# ATMEGA8.net
KiCad netlist of a schematic drawn in EAGLE
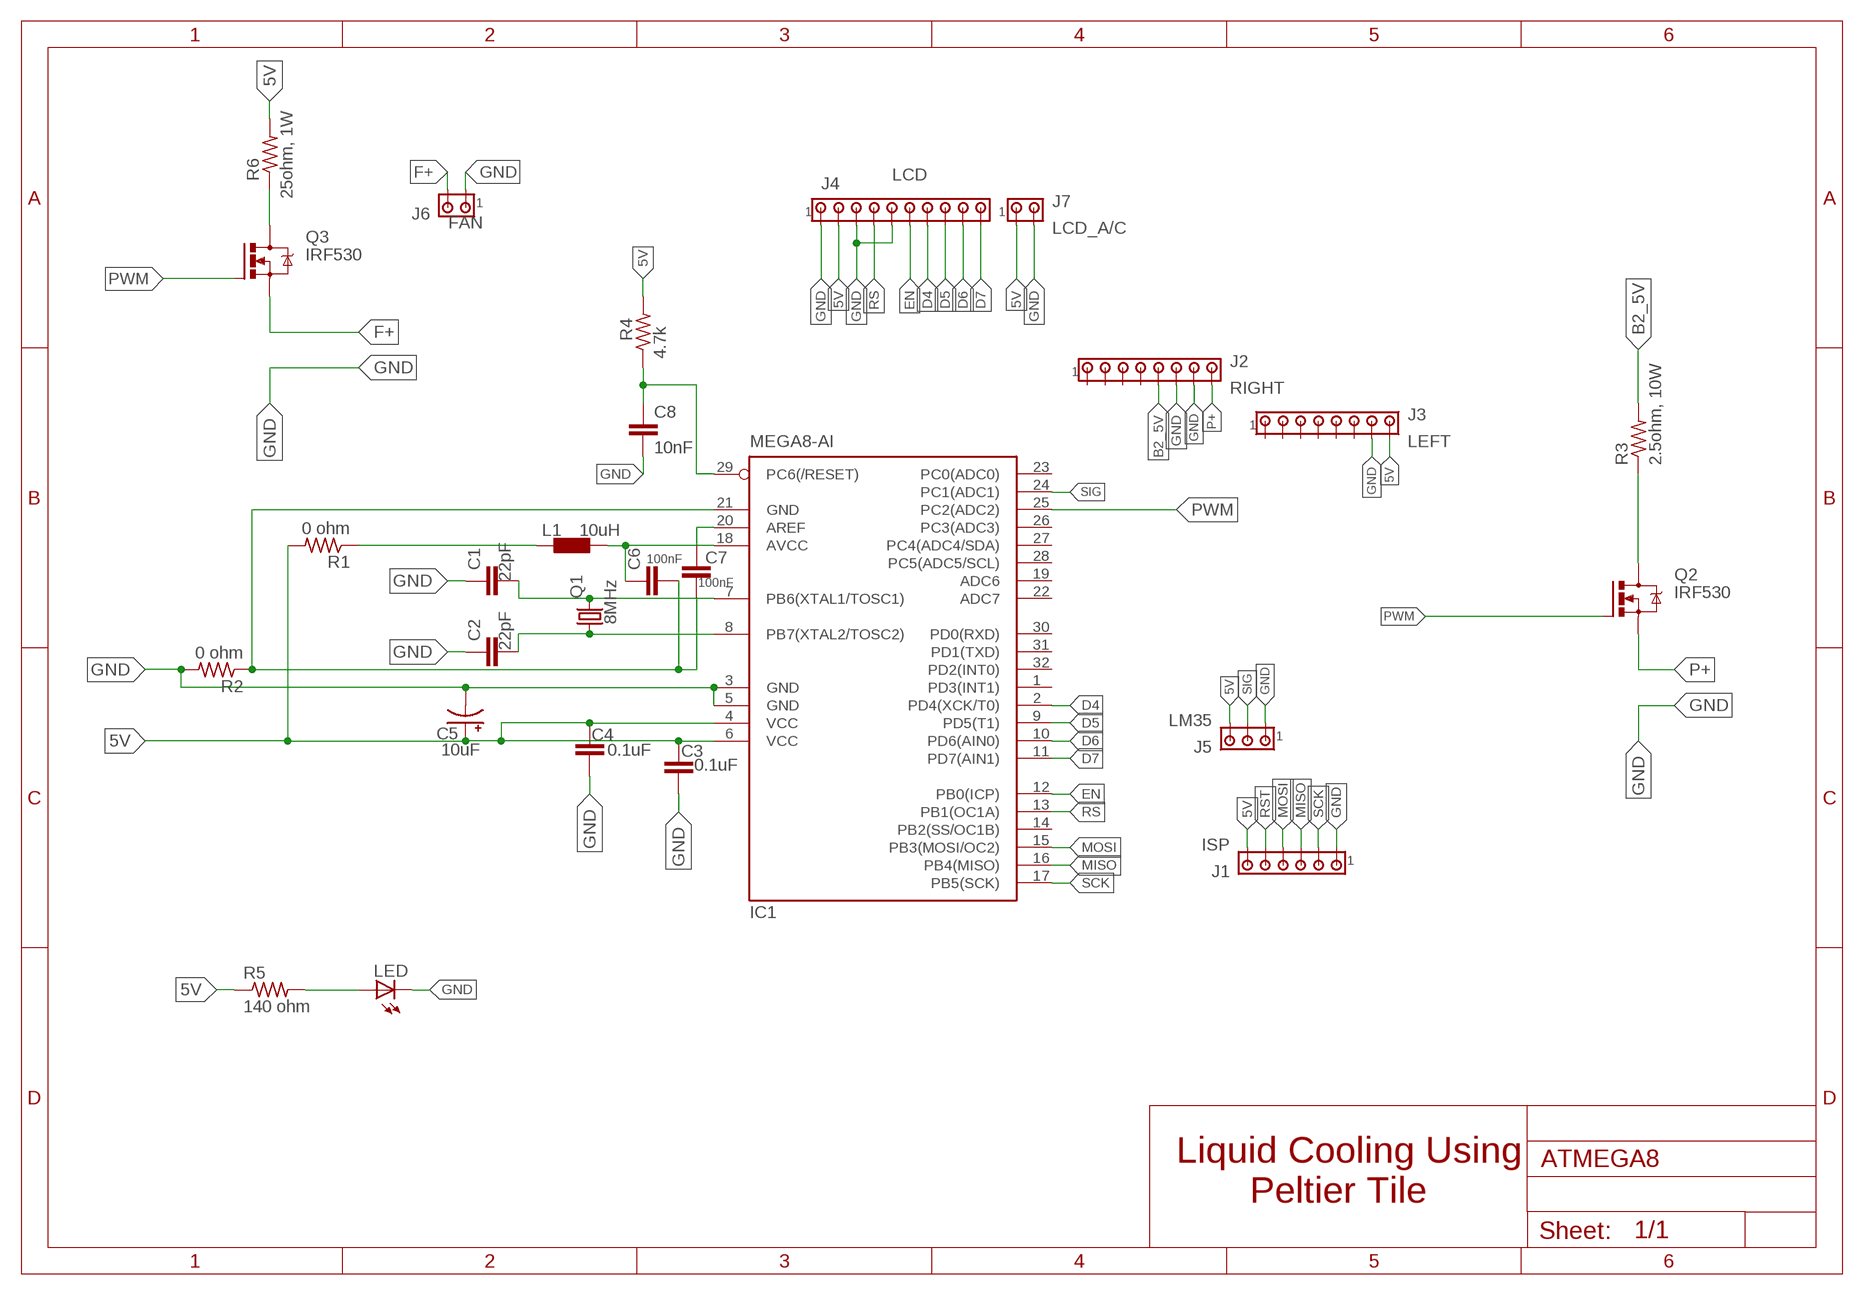
[diagram p0: schematic, sheet 1]

(export (version "E")
  (design (tool "Eeschema 10.0.6"))
  (components
    (comp (ref "C1")
      (value "22pF")
      (footprint "eagle-import:C0805")
      (libsource (lib "eagle-import") (part "C-EUC0805"))
    )
    (comp (ref "C2")
      (value "22pF")
      (footprint "eagle-import:C0805")
      (libsource (lib "eagle-import") (part "C-EUC0805"))
    )
    (comp (ref "C3")
      (value "0.1uF")
      (footprint "eagle-import:C0805")
      (libsource (lib "eagle-import") (part "C-EUC0805"))
    )
    (comp (ref "C4")
      (value "0.1uF")
      (footprint "eagle-import:C0805")
      (libsource (lib "eagle-import") (part "C-EUC0805"))
    )
    (comp (ref "C5")
      (value "10uF")
      (footprint "eagle-import:A_3216-18R")
      (libsource (lib "eagle-import") (part "CPOL-USA/3216-18R"))
    )
    (comp (ref "C6")
      (value "100nF")
      (footprint "eagle-import:C0805")
      (libsource (lib "eagle-import") (part "C-EUC0805"))
    )
    (comp (ref "C7")
      (value "100nF")
      (footprint "eagle-import:C0805")
      (libsource (lib "eagle-import") (part "C-EUC0805"))
    )
    (comp (ref "C8")
      (value "10nF")
      (footprint "eagle-import:C0805")
      (libsource (lib "eagle-import") (part "C-EUC0805"))
    )
    (comp (ref "IC1")
      (value "MEGA8-AI")
      (footprint "eagle-import:TQFP32-08")
      (fields (field (name "MPN") "ATMEGA8-16AU"))
      (libsource (lib "eagle-import") (part "MEGA8-AI"))
    )
    (comp (ref "J1")
      (value "ISP")
      (footprint "eagle-import:10X06MTA")
      (libsource (lib "eagle-import") (part "MTA06-100"))
    )
    (comp (ref "J2")
      (value "RIGHT")
      (footprint "eagle-import:10X08MTA")
      (libsource (lib "eagle-import") (part "MTA08-100"))
    )
    (comp (ref "J3")
      (value "LEFT")
      (footprint "eagle-import:10X08MTA")
      (libsource (lib "eagle-import") (part "MTA08-100"))
    )
    (comp (ref "J4")
      (value "LCD")
      (footprint "eagle-import:10X10MTA")
      (libsource (lib "eagle-import") (part "MTA10-100"))
    )
    (comp (ref "J5")
      (value "LM35")
      (footprint "eagle-import:10X03MTA")
      (libsource (lib "eagle-import") (part "MTA03-100"))
    )
    (comp (ref "J6")
      (value "FAN")
      (footprint "eagle-import:10X02MTA")
      (libsource (lib "eagle-import") (part "MTA02-100"))
    )
    (comp (ref "J7")
      (value "LCD_A/C")
      (footprint "eagle-import:10X02MTA")
      (libsource (lib "eagle-import") (part "MTA02-100"))
    )
    (comp (ref "L1")
      (value "10uH")
      (footprint "eagle-import:0204_7")
      (libsource (lib "eagle-import") (part "L0204/7"))
    )
    (comp (ref "LED")
      (value "RED")
      (footprint "eagle-import:CHIPLED_1206")
      (libsource (lib "eagle-import") (part "LEDCHIPLED_1206"))
    )
    (comp (ref "Q1")
      (value "8MHz")
      (footprint "eagle-import:CSM-7X-DU")
      (libsource (lib "eagle-import") (part "CSM-7X-DU"))
    )
    (comp (ref "Q2")
      (value "IRF530")
      (footprint "eagle-import:TO220BV")
      (libsource (lib "eagle-import") (part "IRF530"))
    )
    (comp (ref "Q3")
      (value "IRF530")
      (footprint "eagle-import:TO220BV")
      (libsource (lib "eagle-import") (part "IRF530"))
    )
    (comp (ref "R1")
      (value "0 ohm")
      (footprint "eagle-import:M0805")
      (libsource (lib "eagle-import") (part "rcl_334_R-US_M0805"))
    )
    (comp (ref "R2")
      (value "0 ohm")
      (footprint "eagle-import:M0805")
      (libsource (lib "eagle-import") (part "rcl_334_R-US_M0805"))
    )
    (comp (ref "R3")
      (value "2.5ohm, 10W")
      (footprint "eagle-import:0207_9")
      (libsource (lib "eagle-import") (part "R-US_0207/9"))
    )
    (comp (ref "R4")
      (value "4.7k")
      (footprint "eagle-import:M0805")
      (libsource (lib "eagle-import") (part "rcl_334_R-US_M0805"))
    )
    (comp (ref "R5")
      (value "140 ohm")
      (footprint "eagle-import:M0805")
      (libsource (lib "eagle-import") (part "rcl_334_R-US_M0805"))
    )
    (comp (ref "R6")
      (value "25ohm, 1W")
      (footprint "eagle-import:0207_10")
      (libsource (lib "eagle-import") (part "R-US_0207/10"))
    )
  )
  (nets
    (net (code "1") (name "5V") (class "Default")
      (node (ref "C3") (pin "1") (pinfunction "1_1") (pintype "passive"))
      (node (ref "C4") (pin "1") (pinfunction "1_1") (pintype "passive"))
      (node (ref "C5") (pin "+") (pinfunction "+_+") (pintype "passive"))
      (node (ref "IC1") (pin "4") (pinfunction "VCC_4") (pintype "power_in"))
      (node (ref "IC1") (pin "6") (pinfunction "VCC_6") (pintype "power_in"))
      (node (ref "J1") (pin "6") (pinfunction "6_6") (pintype "passive"))
      (node (ref "J3") (pin "8") (pinfunction "8_8") (pintype "passive"))
      (node (ref "J4") (pin "2") (pinfunction "2_2") (pintype "passive"))
      (node (ref "J5") (pin "3") (pinfunction "3_3") (pintype "passive"))
      (node (ref "J7") (pin "1") (pinfunction "1_1") (pintype "passive"))
      (node (ref "R1") (pin "2") (pinfunction "2_2") (pintype "passive"))
      (node (ref "R4") (pin "2") (pinfunction "2_2") (pintype "passive"))
      (node (ref "R5") (pin "1") (pinfunction "1_1") (pintype "passive"))
      (node (ref "R6") (pin "2") (pinfunction "2_2") (pintype "passive"))
    )
    (net (code "2") (name "B2_5V") (class "Default")
      (node (ref "J2") (pin "5") (pinfunction "5_5") (pintype "passive"))
      (node (ref "R3") (pin "2") (pinfunction "2_2") (pintype "passive"))
    )
    (net (code "3") (name "D4") (class "Default")
      (node (ref "IC1") (pin "2") (pinfunction "PD4(XCK/T0)_2") (pintype "bidirectional"))
      (node (ref "J4") (pin "7") (pinfunction "7_7") (pintype "passive"))
    )
    (net (code "4") (name "D5") (class "Default")
      (node (ref "IC1") (pin "9") (pinfunction "PD5(T1)_9") (pintype "bidirectional"))
      (node (ref "J4") (pin "8") (pinfunction "8_8") (pintype "passive"))
    )
    (net (code "5") (name "D6") (class "Default")
      (node (ref "IC1") (pin "10") (pinfunction "PD6(AIN0)_10") (pintype "bidirectional"))
      (node (ref "J4") (pin "9") (pinfunction "9_9") (pintype "passive"))
    )
    (net (code "6") (name "D7") (class "Default")
      (node (ref "IC1") (pin "11") (pinfunction "PD7(AIN1)_11") (pintype "bidirectional"))
      (node (ref "J4") (pin "10") (pinfunction "10_10") (pintype "passive"))
    )
    (net (code "7") (name "EN") (class "Default")
      (node (ref "IC1") (pin "12") (pinfunction "PB0(ICP)_12") (pintype "bidirectional"))
      (node (ref "J4") (pin "6") (pinfunction "6_6") (pintype "passive"))
    )
    (net (code "8") (name "F+") (class "Default")
      (node (ref "J6") (pin "2") (pinfunction "2_2") (pintype "passive"))
      (node (ref "Q3") (pin "S") (pinfunction "S_S") (pintype "passive"))
    )
    (net (code "9") (name "GND") (class "Default")
      (node (ref "C1") (pin "1") (pinfunction "1_1") (pintype "passive"))
      (node (ref "C2") (pin "1") (pinfunction "1_1") (pintype "passive"))
      (node (ref "C3") (pin "2") (pinfunction "2_2") (pintype "passive"))
      (node (ref "C4") (pin "2") (pinfunction "2_2") (pintype "passive"))
      (node (ref "C5") (pin "-") (pinfunction "-_-") (pintype "passive"))
      (node (ref "C8") (pin "2") (pinfunction "2_2") (pintype "passive"))
      (node (ref "IC1") (pin "3") (pinfunction "GND_3") (pintype "power_in"))
      (node (ref "IC1") (pin "5") (pinfunction "GND_5") (pintype "power_in"))
      (node (ref "J1") (pin "1") (pinfunction "1_1") (pintype "passive"))
      (node (ref "J2") (pin "6") (pinfunction "6_6") (pintype "passive"))
      (node (ref "J2") (pin "7") (pinfunction "7_7") (pintype "passive"))
      (node (ref "J3") (pin "7") (pinfunction "7_7") (pintype "passive"))
      (node (ref "J4") (pin "1") (pinfunction "1_1") (pintype "passive"))
      (node (ref "J4") (pin "3") (pinfunction "3_3") (pintype "passive"))
      (node (ref "J4") (pin "5") (pinfunction "5_5") (pintype "passive"))
      (node (ref "J5") (pin "1") (pinfunction "1_1") (pintype "passive"))
      (node (ref "J6") (pin "1") (pinfunction "1_1") (pintype "passive"))
      (node (ref "J7") (pin "2") (pinfunction "2_2") (pintype "passive"))
      (node (ref "LED") (pin "C") (pinfunction "C_C") (pintype "passive"))
      (node (ref "R2") (pin "2") (pinfunction "2_2") (pintype "passive"))
    )
    (net (code "10") (name "MISO") (class "Default")
      (node (ref "IC1") (pin "16") (pinfunction "PB4(MISO)_16") (pintype "bidirectional"))
      (node (ref "J1") (pin "3") (pinfunction "3_3") (pintype "passive"))
    )
    (net (code "11") (name "MOSI") (class "Default")
      (node (ref "IC1") (pin "15") (pinfunction "PB3(MOSI/OC2)_15") (pintype "bidirectional"))
      (node (ref "J1") (pin "4") (pinfunction "4_4") (pintype "passive"))
    )
    (net (code "12") (name "Net-(C6-Pad2)") (class "Default")
      (node (ref "C6") (pin "2") (pinfunction "2_2") (pintype "passive"))
      (node (ref "C7") (pin "2") (pinfunction "2_2") (pintype "passive"))
      (node (ref "IC1") (pin "21") (pinfunction "GND_21") (pintype "power_in"))
      (node (ref "R2") (pin "1") (pinfunction "1_1") (pintype "passive"))
    )
    (net (code "13") (name "Net-(IC1-AREF)") (class "Default")
      (node (ref "C7") (pin "1") (pinfunction "1_1") (pintype "passive"))
      (node (ref "IC1") (pin "20") (pinfunction "AREF_20") (pintype "passive"))
    )
    (net (code "14") (name "Net-(IC1-AVCC)") (class "Default")
      (node (ref "C6") (pin "1") (pinfunction "1_1") (pintype "passive"))
      (node (ref "IC1") (pin "18") (pinfunction "AVCC_18") (pintype "power_in"))
      (node (ref "L1") (pin "2") (pinfunction "2_2") (pintype "passive"))
    )
    (net (code "15") (name "Net-(IC1-PB6(XTAL1{slash}TOSC1))") (class "Default")
      (node (ref "C1") (pin "2") (pinfunction "2_2") (pintype "passive"))
      (node (ref "IC1") (pin "7") (pinfunction "PB6(XTAL1/TOSC1)_7") (pintype "bidirectional"))
      (node (ref "Q1") (pin "2") (pinfunction "2_2") (pintype "passive"))
    )
    (net (code "16") (name "Net-(IC1-PB7(XTAL2{slash}TOSC2))") (class "Default")
      (node (ref "C2") (pin "2") (pinfunction "2_2") (pintype "passive"))
      (node (ref "IC1") (pin "8") (pinfunction "PB7(XTAL2/TOSC2)_8") (pintype "bidirectional"))
      (node (ref "Q1") (pin "1") (pinfunction "1_1") (pintype "passive"))
    )
    (net (code "17") (name "Net-(IC1-PC6({slash}RESET))") (class "Default")
      (node (ref "C8") (pin "1") (pinfunction "1_1") (pintype "passive"))
      (node (ref "IC1") (pin "29") (pinfunction "PC6(/RESET)_29") (pintype "bidirectional"))
      (node (ref "R4") (pin "1") (pinfunction "1_1") (pintype "passive"))
    )
    (net (code "18") (name "Net-(L1-Pad1)") (class "Default")
      (node (ref "L1") (pin "1") (pinfunction "1_1") (pintype "passive"))
      (node (ref "R1") (pin "1") (pinfunction "1_1") (pintype "passive"))
    )
    (net (code "19") (name "Net-(LED-PadA)") (class "Default")
      (node (ref "LED") (pin "A") (pinfunction "A_A") (pintype "passive"))
      (node (ref "R5") (pin "2") (pinfunction "2_2") (pintype "passive"))
    )
    (net (code "20") (name "Net-(Q2-PadD)") (class "Default")
      (node (ref "Q2") (pin "D") (pinfunction "D_D") (pintype "passive"))
      (node (ref "R3") (pin "1") (pinfunction "1_1") (pintype "passive"))
    )
    (net (code "21") (name "Net-(Q3-PadD)") (class "Default")
      (node (ref "Q3") (pin "D") (pinfunction "D_D") (pintype "passive"))
      (node (ref "R6") (pin "1") (pinfunction "1_1") (pintype "passive"))
    )
    (net (code "22") (name "P+") (class "Default")
      (node (ref "J2") (pin "8") (pinfunction "8_8") (pintype "passive"))
      (node (ref "Q2") (pin "S") (pinfunction "S_S") (pintype "passive"))
    )
    (net (code "23") (name "PWM") (class "Default")
      (node (ref "IC1") (pin "25") (pinfunction "PC2(ADC2)_25") (pintype "bidirectional"))
      (node (ref "Q2") (pin "G") (pinfunction "G_G") (pintype "passive"))
      (node (ref "Q3") (pin "G") (pinfunction "G_G") (pintype "passive"))
    )
    (net (code "24") (name "RS") (class "Default")
      (node (ref "IC1") (pin "13") (pinfunction "PB1(OC1A)_13") (pintype "bidirectional"))
      (node (ref "J4") (pin "4") (pinfunction "4_4") (pintype "passive"))
    )
    (net (code "25") (name "RST") (class "Default")
      (node (ref "J1") (pin "5") (pinfunction "5_5") (pintype "passive"))
    )
    (net (code "26") (name "SCK") (class "Default")
      (node (ref "IC1") (pin "17") (pinfunction "PB5(SCK)_17") (pintype "bidirectional"))
      (node (ref "J1") (pin "2") (pinfunction "2_2") (pintype "passive"))
    )
    (net (code "27") (name "SIG") (class "Default")
      (node (ref "IC1") (pin "24") (pinfunction "PC1(ADC1)_24") (pintype "bidirectional"))
      (node (ref "J5") (pin "2") (pinfunction "2_2") (pintype "passive"))
    )
    (net (code "28") (name "unconnected-(IC1-ADC6-Pad19)") (class "Default")
      (node (ref "IC1") (pin "19") (pinfunction "ADC6_19") (pintype "bidirectional"))
    )
    (net (code "29") (name "unconnected-(IC1-ADC7-Pad22)") (class "Default")
      (node (ref "IC1") (pin "22") (pinfunction "ADC7_22") (pintype "bidirectional"))
    )
    (net (code "30") (name "unconnected-(IC1-PB2(SS{slash}OC1B)-Pad14)") (class "Default")
      (node (ref "IC1") (pin "14") (pinfunction "PB2(SS/OC1B)_14") (pintype "bidirectional"))
    )
    (net (code "31") (name "unconnected-(IC1-PC0(ADC0)-Pad23)") (class "Default")
      (node (ref "IC1") (pin "23") (pinfunction "PC0(ADC0)_23") (pintype "bidirectional"))
    )
    (net (code "32") (name "unconnected-(IC1-PC3(ADC3)-Pad26)") (class "Default")
      (node (ref "IC1") (pin "26") (pinfunction "PC3(ADC3)_26") (pintype "bidirectional"))
    )
    (net (code "33") (name "unconnected-(IC1-PC4(ADC4{slash}SDA)-Pad27)") (class "Default")
      (node (ref "IC1") (pin "27") (pinfunction "PC4(ADC4/SDA)_27") (pintype "bidirectional"))
    )
    (net (code "34") (name "unconnected-(IC1-PC5(ADC5{slash}SCL)-Pad28)") (class "Default")
      (node (ref "IC1") (pin "28") (pinfunction "PC5(ADC5/SCL)_28") (pintype "bidirectional"))
    )
    (net (code "35") (name "unconnected-(IC1-PD0(RXD)-Pad30)") (class "Default")
      (node (ref "IC1") (pin "30") (pinfunction "PD0(RXD)_30") (pintype "bidirectional"))
    )
    (net (code "36") (name "unconnected-(IC1-PD1(TXD)-Pad31)") (class "Default")
      (node (ref "IC1") (pin "31") (pinfunction "PD1(TXD)_31") (pintype "bidirectional"))
    )
    (net (code "37") (name "unconnected-(IC1-PD2(INT0)-Pad32)") (class "Default")
      (node (ref "IC1") (pin "32") (pinfunction "PD2(INT0)_32") (pintype "bidirectional"))
    )
    (net (code "38") (name "unconnected-(IC1-PD3(INT1)-Pad1)") (class "Default")
      (node (ref "IC1") (pin "1") (pinfunction "PD3(INT1)_1") (pintype "bidirectional"))
    )
    (net (code "39") (name "unconnected-(J2-Pad1)") (class "Default")
      (node (ref "J2") (pin "1") (pinfunction "1_1") (pintype "passive"))
    )
    (net (code "40") (name "unconnected-(J2-Pad2)") (class "Default")
      (node (ref "J2") (pin "2") (pinfunction "2_2") (pintype "passive"))
    )
    (net (code "41") (name "unconnected-(J2-Pad3)") (class "Default")
      (node (ref "J2") (pin "3") (pinfunction "3_3") (pintype "passive"))
    )
    (net (code "42") (name "unconnected-(J2-Pad4)") (class "Default")
      (node (ref "J2") (pin "4") (pinfunction "4_4") (pintype "passive"))
    )
    (net (code "43") (name "unconnected-(J3-Pad1)") (class "Default")
      (node (ref "J3") (pin "1") (pinfunction "1_1") (pintype "passive"))
    )
    (net (code "44") (name "unconnected-(J3-Pad2)") (class "Default")
      (node (ref "J3") (pin "2") (pinfunction "2_2") (pintype "passive"))
    )
    (net (code "45") (name "unconnected-(J3-Pad3)") (class "Default")
      (node (ref "J3") (pin "3") (pinfunction "3_3") (pintype "passive"))
    )
    (net (code "46") (name "unconnected-(J3-Pad4)") (class "Default")
      (node (ref "J3") (pin "4") (pinfunction "4_4") (pintype "passive"))
    )
    (net (code "47") (name "unconnected-(J3-Pad5)") (class "Default")
      (node (ref "J3") (pin "5") (pinfunction "5_5") (pintype "passive"))
    )
    (net (code "48") (name "unconnected-(J3-Pad6)") (class "Default")
      (node (ref "J3") (pin "6") (pinfunction "6_6") (pintype "passive"))
    )
  )
)
